# Program_Counter.net
KiCad netlist of a schematic drawn in EAGLE
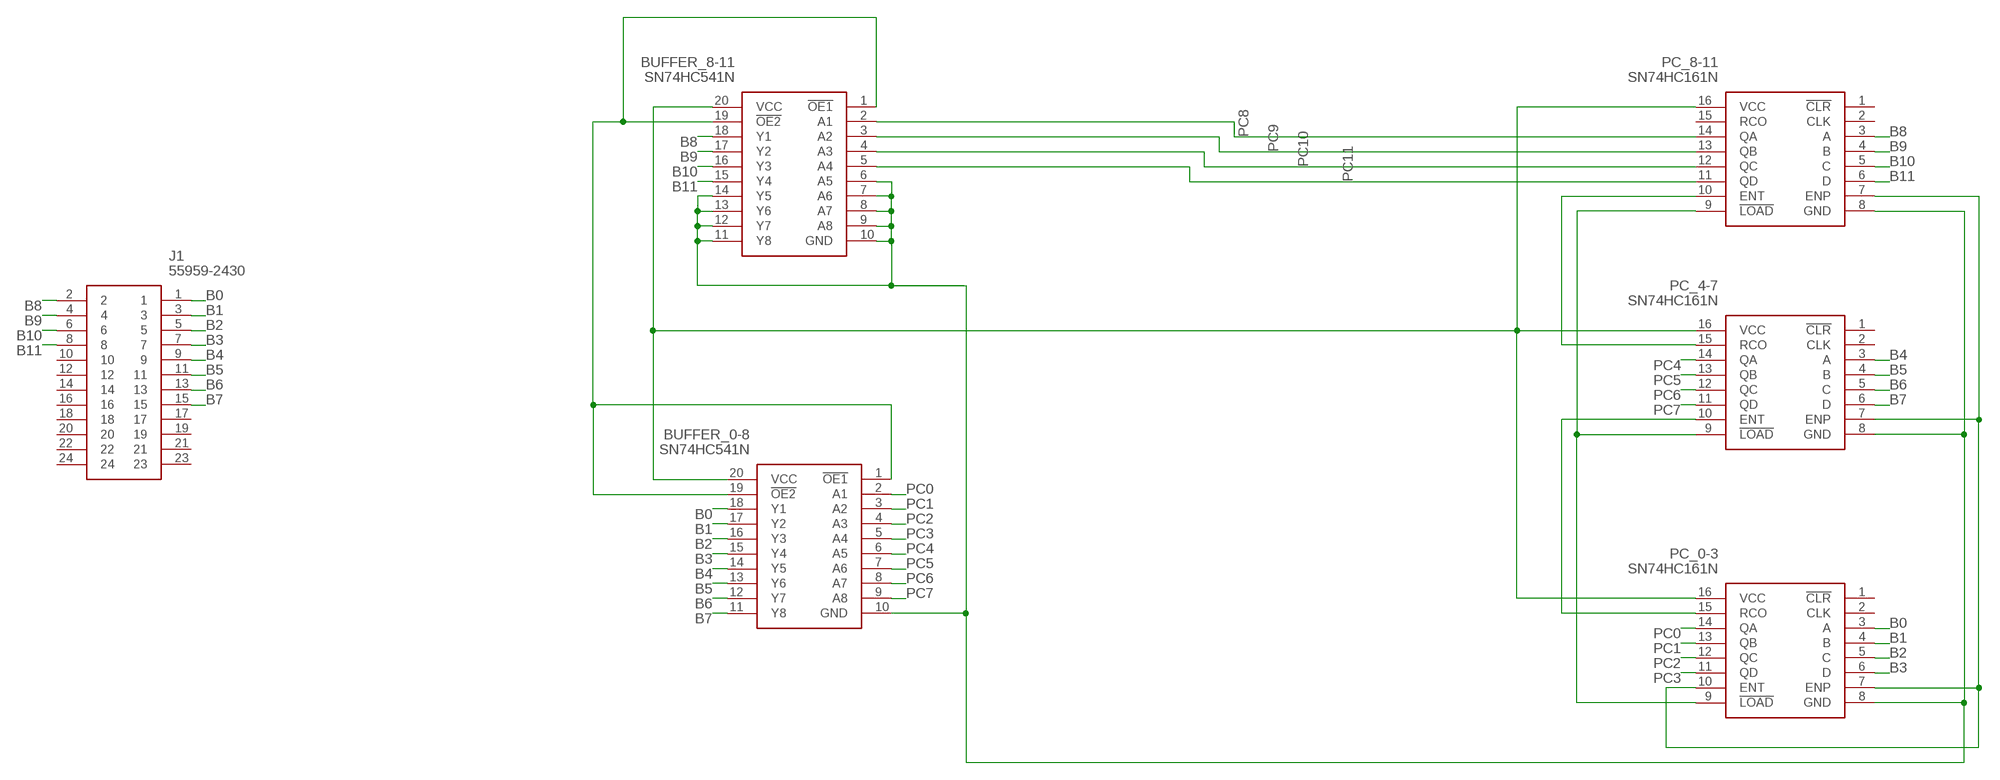
[diagram p0: schematic, sheet 1]

(export (version "E")
  (design (tool "Eeschema 10.0.6"))
  (components
    (comp (ref "BUFFER_0-8")
      (value "SN74HC541N")
      (footprint "eagle-import:DIP794W53P254L2540H508Q20N")
      (fields (field (name "MOUSER_PART_NUMBER") "595-SN74HC541N"))
      (libsource (lib "eagle-import") (part "SN74HC541N"))
    )
    (comp (ref "BUFFER_8-11")
      (value "SN74HC541N")
      (footprint "eagle-import:DIP794W53P254L2540H508Q20N")
      (fields (field (name "MOUSER_PART_NUMBER") "595-SN74HC541N"))
      (libsource (lib "eagle-import") (part "SN74HC541N"))
    )
    (comp (ref "J1")
      (value "55959-2430")
      (footprint "eagle-import:559592430")
      (fields (field (name "MOUSER_PART_NUMBER") "538-55959-2430"))
      (libsource (lib "eagle-import") (part "55959-2430"))
    )
    (comp (ref "PC_0-3")
      (value "SN74HC161N")
      (footprint "eagle-import:DIP794W53P254L1930H508Q16N")
      (fields (field (name "MOUSER_PART_NUMBER") "595-SN74HC161N"))
      (libsource (lib "eagle-import") (part "SN74HC161N"))
    )
    (comp (ref "PC_4-7")
      (value "SN74HC161N")
      (footprint "eagle-import:DIP794W53P254L1930H508Q16N")
      (fields (field (name "MOUSER_PART_NUMBER") "595-SN74HC161N"))
      (libsource (lib "eagle-import") (part "SN74HC161N"))
    )
    (comp (ref "PC_8-11")
      (value "SN74HC161N")
      (footprint "eagle-import:DIP794W53P254L1930H508Q16N")
      (fields (field (name "MOUSER_PART_NUMBER") "595-SN74HC161N"))
      (libsource (lib "eagle-import") (part "SN74HC161N"))
    )
  )
  (nets
    (net (code "1") (name "/B0") (class "Default")
      (node (ref "BUFFER_0-8") (pin "18") (pinfunction "Y1_18") (pintype "bidirectional"))
      (node (ref "J1") (pin "1") (pinfunction "1_1") (pintype "bidirectional"))
      (node (ref "PC_0-3") (pin "3") (pinfunction "A_3") (pintype "bidirectional"))
    )
    (net (code "2") (name "/B1") (class "Default")
      (node (ref "BUFFER_0-8") (pin "17") (pinfunction "Y2_17") (pintype "bidirectional"))
      (node (ref "J1") (pin "3") (pinfunction "3_3") (pintype "bidirectional"))
      (node (ref "PC_0-3") (pin "4") (pinfunction "B_4") (pintype "bidirectional"))
    )
    (net (code "3") (name "/B2") (class "Default")
      (node (ref "BUFFER_0-8") (pin "16") (pinfunction "Y3_16") (pintype "bidirectional"))
      (node (ref "J1") (pin "5") (pinfunction "5_5") (pintype "bidirectional"))
      (node (ref "PC_0-3") (pin "5") (pinfunction "C_5") (pintype "bidirectional"))
    )
    (net (code "4") (name "/B3") (class "Default")
      (node (ref "BUFFER_0-8") (pin "15") (pinfunction "Y4_15") (pintype "bidirectional"))
      (node (ref "J1") (pin "7") (pinfunction "7_7") (pintype "bidirectional"))
      (node (ref "PC_0-3") (pin "6") (pinfunction "D_6") (pintype "bidirectional"))
    )
    (net (code "5") (name "/B4") (class "Default")
      (node (ref "BUFFER_0-8") (pin "14") (pinfunction "Y5_14") (pintype "bidirectional"))
      (node (ref "J1") (pin "9") (pinfunction "9_9") (pintype "bidirectional"))
      (node (ref "PC_4-7") (pin "3") (pinfunction "A_3") (pintype "bidirectional"))
    )
    (net (code "6") (name "/B5") (class "Default")
      (node (ref "BUFFER_0-8") (pin "13") (pinfunction "Y6_13") (pintype "bidirectional"))
      (node (ref "J1") (pin "11") (pinfunction "11_11") (pintype "bidirectional"))
      (node (ref "PC_4-7") (pin "4") (pinfunction "B_4") (pintype "bidirectional"))
    )
    (net (code "7") (name "/B6") (class "Default")
      (node (ref "BUFFER_0-8") (pin "12") (pinfunction "Y7_12") (pintype "bidirectional"))
      (node (ref "J1") (pin "13") (pinfunction "13_13") (pintype "bidirectional"))
      (node (ref "PC_4-7") (pin "5") (pinfunction "C_5") (pintype "bidirectional"))
    )
    (net (code "8") (name "/B7") (class "Default")
      (node (ref "BUFFER_0-8") (pin "11") (pinfunction "Y8_11") (pintype "bidirectional"))
      (node (ref "J1") (pin "15") (pinfunction "15_15") (pintype "bidirectional"))
      (node (ref "PC_4-7") (pin "6") (pinfunction "D_6") (pintype "bidirectional"))
    )
    (net (code "9") (name "/B8") (class "Default")
      (node (ref "BUFFER_8-11") (pin "18") (pinfunction "Y1_18") (pintype "bidirectional"))
      (node (ref "J1") (pin "2") (pinfunction "2_2") (pintype "bidirectional"))
      (node (ref "PC_8-11") (pin "3") (pinfunction "A_3") (pintype "bidirectional"))
    )
    (net (code "10") (name "/B9") (class "Default")
      (node (ref "BUFFER_8-11") (pin "17") (pinfunction "Y2_17") (pintype "bidirectional"))
      (node (ref "J1") (pin "4") (pinfunction "4_4") (pintype "bidirectional"))
      (node (ref "PC_8-11") (pin "4") (pinfunction "B_4") (pintype "bidirectional"))
    )
    (net (code "11") (name "/B10") (class "Default")
      (node (ref "BUFFER_8-11") (pin "16") (pinfunction "Y3_16") (pintype "bidirectional"))
      (node (ref "J1") (pin "6") (pinfunction "6_6") (pintype "bidirectional"))
      (node (ref "PC_8-11") (pin "5") (pinfunction "C_5") (pintype "bidirectional"))
    )
    (net (code "12") (name "/B11") (class "Default")
      (node (ref "BUFFER_8-11") (pin "15") (pinfunction "Y4_15") (pintype "bidirectional"))
      (node (ref "J1") (pin "8") (pinfunction "8_8") (pintype "bidirectional"))
      (node (ref "PC_8-11") (pin "6") (pinfunction "D_6") (pintype "bidirectional"))
    )
    (net (code "13") (name "/PC0") (class "Default")
      (node (ref "BUFFER_0-8") (pin "2") (pinfunction "A1_2") (pintype "bidirectional"))
      (node (ref "PC_0-3") (pin "14") (pinfunction "QA_14") (pintype "bidirectional"))
    )
    (net (code "14") (name "/PC1") (class "Default")
      (node (ref "BUFFER_0-8") (pin "3") (pinfunction "A2_3") (pintype "bidirectional"))
      (node (ref "PC_0-3") (pin "13") (pinfunction "QB_13") (pintype "bidirectional"))
    )
    (net (code "15") (name "/PC2") (class "Default")
      (node (ref "BUFFER_0-8") (pin "4") (pinfunction "A3_4") (pintype "bidirectional"))
      (node (ref "PC_0-3") (pin "12") (pinfunction "QC_12") (pintype "bidirectional"))
    )
    (net (code "16") (name "/PC3") (class "Default")
      (node (ref "BUFFER_0-8") (pin "5") (pinfunction "A4_5") (pintype "bidirectional"))
      (node (ref "PC_0-3") (pin "11") (pinfunction "QD_11") (pintype "bidirectional"))
    )
    (net (code "17") (name "/PC4") (class "Default")
      (node (ref "BUFFER_0-8") (pin "6") (pinfunction "A5_6") (pintype "bidirectional"))
      (node (ref "PC_4-7") (pin "14") (pinfunction "QA_14") (pintype "bidirectional"))
    )
    (net (code "18") (name "/PC5") (class "Default")
      (node (ref "BUFFER_0-8") (pin "7") (pinfunction "A6_7") (pintype "bidirectional"))
      (node (ref "PC_4-7") (pin "13") (pinfunction "QB_13") (pintype "bidirectional"))
    )
    (net (code "19") (name "/PC6") (class "Default")
      (node (ref "BUFFER_0-8") (pin "8") (pinfunction "A7_8") (pintype "bidirectional"))
      (node (ref "PC_4-7") (pin "12") (pinfunction "QC_12") (pintype "bidirectional"))
    )
    (net (code "20") (name "/PC7") (class "Default")
      (node (ref "BUFFER_0-8") (pin "9") (pinfunction "A8_9") (pintype "bidirectional"))
      (node (ref "PC_4-7") (pin "11") (pinfunction "QD_11") (pintype "bidirectional"))
    )
    (net (code "21") (name "/PC8") (class "Default")
      (node (ref "BUFFER_8-11") (pin "2") (pinfunction "A1_2") (pintype "bidirectional"))
      (node (ref "PC_8-11") (pin "14") (pinfunction "QA_14") (pintype "bidirectional"))
    )
    (net (code "22") (name "/PC9") (class "Default")
      (node (ref "BUFFER_8-11") (pin "3") (pinfunction "A2_3") (pintype "bidirectional"))
      (node (ref "PC_8-11") (pin "13") (pinfunction "QB_13") (pintype "bidirectional"))
    )
    (net (code "23") (name "/PC10") (class "Default")
      (node (ref "BUFFER_8-11") (pin "4") (pinfunction "A3_4") (pintype "bidirectional"))
      (node (ref "PC_8-11") (pin "12") (pinfunction "QC_12") (pintype "bidirectional"))
    )
    (net (code "24") (name "/PC11") (class "Default")
      (node (ref "BUFFER_8-11") (pin "5") (pinfunction "A4_5") (pintype "bidirectional"))
      (node (ref "PC_8-11") (pin "11") (pinfunction "QD_11") (pintype "bidirectional"))
    )
    (net (code "25") (name "Net-(BUFFER_0-8-GND)") (class "Default")
      (node (ref "BUFFER_0-8") (pin "10") (pinfunction "GND_10") (pintype "bidirectional"))
      (node (ref "BUFFER_8-11") (pin "10") (pinfunction "GND_10") (pintype "bidirectional"))
      (node (ref "BUFFER_8-11") (pin "11") (pinfunction "Y8_11") (pintype "bidirectional"))
      (node (ref "BUFFER_8-11") (pin "12") (pinfunction "Y7_12") (pintype "bidirectional"))
      (node (ref "BUFFER_8-11") (pin "13") (pinfunction "Y6_13") (pintype "bidirectional"))
      (node (ref "BUFFER_8-11") (pin "14") (pinfunction "Y5_14") (pintype "bidirectional"))
      (node (ref "BUFFER_8-11") (pin "6") (pinfunction "A5_6") (pintype "bidirectional"))
      (node (ref "BUFFER_8-11") (pin "7") (pinfunction "A6_7") (pintype "bidirectional"))
      (node (ref "BUFFER_8-11") (pin "8") (pinfunction "A7_8") (pintype "bidirectional"))
      (node (ref "BUFFER_8-11") (pin "9") (pinfunction "A8_9") (pintype "bidirectional"))
      (node (ref "PC_0-3") (pin "8") (pinfunction "GND_8") (pintype "bidirectional"))
      (node (ref "PC_4-7") (pin "8") (pinfunction "GND_8") (pintype "bidirectional"))
      (node (ref "PC_8-11") (pin "8") (pinfunction "GND_8") (pintype "bidirectional"))
    )
    (net (code "26") (name "Net-(BUFFER_0-8-VCC)") (class "Default")
      (node (ref "BUFFER_0-8") (pin "20") (pinfunction "VCC_20") (pintype "bidirectional"))
      (node (ref "BUFFER_8-11") (pin "20") (pinfunction "VCC_20") (pintype "bidirectional"))
      (node (ref "PC_0-3") (pin "16") (pinfunction "VCC_16") (pintype "bidirectional"))
      (node (ref "PC_4-7") (pin "16") (pinfunction "VCC_16") (pintype "bidirectional"))
      (node (ref "PC_8-11") (pin "16") (pinfunction "VCC_16") (pintype "bidirectional"))
    )
    (net (code "27") (name "Net-(BUFFER_0-8-~{OE1})") (class "Default")
      (node (ref "BUFFER_0-8") (pin "1") (pinfunction "~{OE1}_1") (pintype "bidirectional"))
      (node (ref "BUFFER_0-8") (pin "19") (pinfunction "~{OE2}_19") (pintype "bidirectional"))
      (node (ref "BUFFER_8-11") (pin "1") (pinfunction "~{OE1}_1") (pintype "bidirectional"))
      (node (ref "BUFFER_8-11") (pin "19") (pinfunction "~{OE2}_19") (pintype "bidirectional"))
    )
    (net (code "28") (name "Net-(PC_0-3-ENP)") (class "Default")
      (node (ref "PC_0-3") (pin "10") (pinfunction "ENT_10") (pintype "bidirectional"))
      (node (ref "PC_0-3") (pin "7") (pinfunction "ENP_7") (pintype "bidirectional"))
      (node (ref "PC_4-7") (pin "7") (pinfunction "ENP_7") (pintype "bidirectional"))
      (node (ref "PC_8-11") (pin "7") (pinfunction "ENP_7") (pintype "bidirectional"))
    )
    (net (code "29") (name "Net-(PC_0-3-RCO)") (class "Default")
      (node (ref "PC_0-3") (pin "15") (pinfunction "RCO_15") (pintype "bidirectional"))
      (node (ref "PC_4-7") (pin "10") (pinfunction "ENT_10") (pintype "bidirectional"))
    )
    (net (code "30") (name "Net-(PC_0-3-~{LOAD})") (class "Default")
      (node (ref "PC_0-3") (pin "9") (pinfunction "~{LOAD}_9") (pintype "bidirectional"))
      (node (ref "PC_4-7") (pin "9") (pinfunction "~{LOAD}_9") (pintype "bidirectional"))
      (node (ref "PC_8-11") (pin "9") (pinfunction "~{LOAD}_9") (pintype "bidirectional"))
    )
    (net (code "31") (name "Net-(PC_4-7-RCO)") (class "Default")
      (node (ref "PC_4-7") (pin "15") (pinfunction "RCO_15") (pintype "bidirectional"))
      (node (ref "PC_8-11") (pin "10") (pinfunction "ENT_10") (pintype "bidirectional"))
    )
    (net (code "32") (name "unconnected-(J1-Pad10)") (class "Default")
      (node (ref "J1") (pin "10") (pinfunction "10_10") (pintype "bidirectional"))
    )
    (net (code "33") (name "unconnected-(J1-Pad12)") (class "Default")
      (node (ref "J1") (pin "12") (pinfunction "12_12") (pintype "bidirectional"))
    )
    (net (code "34") (name "unconnected-(J1-Pad14)") (class "Default")
      (node (ref "J1") (pin "14") (pinfunction "14_14") (pintype "bidirectional"))
    )
    (net (code "35") (name "unconnected-(J1-Pad16)") (class "Default")
      (node (ref "J1") (pin "16") (pinfunction "16_16") (pintype "bidirectional"))
    )
    (net (code "36") (name "unconnected-(J1-Pad17)") (class "Default")
      (node (ref "J1") (pin "17") (pinfunction "17_17") (pintype "bidirectional"))
    )
    (net (code "37") (name "unconnected-(J1-Pad18)") (class "Default")
      (node (ref "J1") (pin "18") (pinfunction "18_18") (pintype "bidirectional"))
    )
    (net (code "38") (name "unconnected-(J1-Pad19)") (class "Default")
      (node (ref "J1") (pin "19") (pinfunction "19_19") (pintype "bidirectional"))
    )
    (net (code "39") (name "unconnected-(J1-Pad20)") (class "Default")
      (node (ref "J1") (pin "20") (pinfunction "20_20") (pintype "bidirectional"))
    )
    (net (code "40") (name "unconnected-(J1-Pad21)") (class "Default")
      (node (ref "J1") (pin "21") (pinfunction "21_21") (pintype "bidirectional"))
    )
    (net (code "41") (name "unconnected-(J1-Pad22)") (class "Default")
      (node (ref "J1") (pin "22") (pinfunction "22_22") (pintype "bidirectional"))
    )
    (net (code "42") (name "unconnected-(J1-Pad23)") (class "Default")
      (node (ref "J1") (pin "23") (pinfunction "23_23") (pintype "bidirectional"))
    )
    (net (code "43") (name "unconnected-(J1-Pad24)") (class "Default")
      (node (ref "J1") (pin "24") (pinfunction "24_24") (pintype "bidirectional"))
    )
    (net (code "44") (name "unconnected-(PC_0-3-CLK-Pad2)") (class "Default")
      (node (ref "PC_0-3") (pin "2") (pinfunction "CLK_2") (pintype "bidirectional"))
    )
    (net (code "45") (name "unconnected-(PC_0-3-~{CLR}-Pad1)") (class "Default")
      (node (ref "PC_0-3") (pin "1") (pinfunction "~{CLR}_1") (pintype "bidirectional"))
    )
    (net (code "46") (name "unconnected-(PC_4-7-CLK-Pad2)") (class "Default")
      (node (ref "PC_4-7") (pin "2") (pinfunction "CLK_2") (pintype "bidirectional"))
    )
    (net (code "47") (name "unconnected-(PC_4-7-~{CLR}-Pad1)") (class "Default")
      (node (ref "PC_4-7") (pin "1") (pinfunction "~{CLR}_1") (pintype "bidirectional"))
    )
    (net (code "48") (name "unconnected-(PC_8-11-CLK-Pad2)") (class "Default")
      (node (ref "PC_8-11") (pin "2") (pinfunction "CLK_2") (pintype "bidirectional"))
    )
    (net (code "49") (name "unconnected-(PC_8-11-RCO-Pad15)") (class "Default")
      (node (ref "PC_8-11") (pin "15") (pinfunction "RCO_15") (pintype "bidirectional"))
    )
    (net (code "50") (name "unconnected-(PC_8-11-~{CLR}-Pad1)") (class "Default")
      (node (ref "PC_8-11") (pin "1") (pinfunction "~{CLR}_1") (pintype "bidirectional"))
    )
  )
)
